# Schematic_TurtleAuth_-_Stm32GPG_2022-05-.net
KiCad netlist of a schematic drawn in EasyEDA
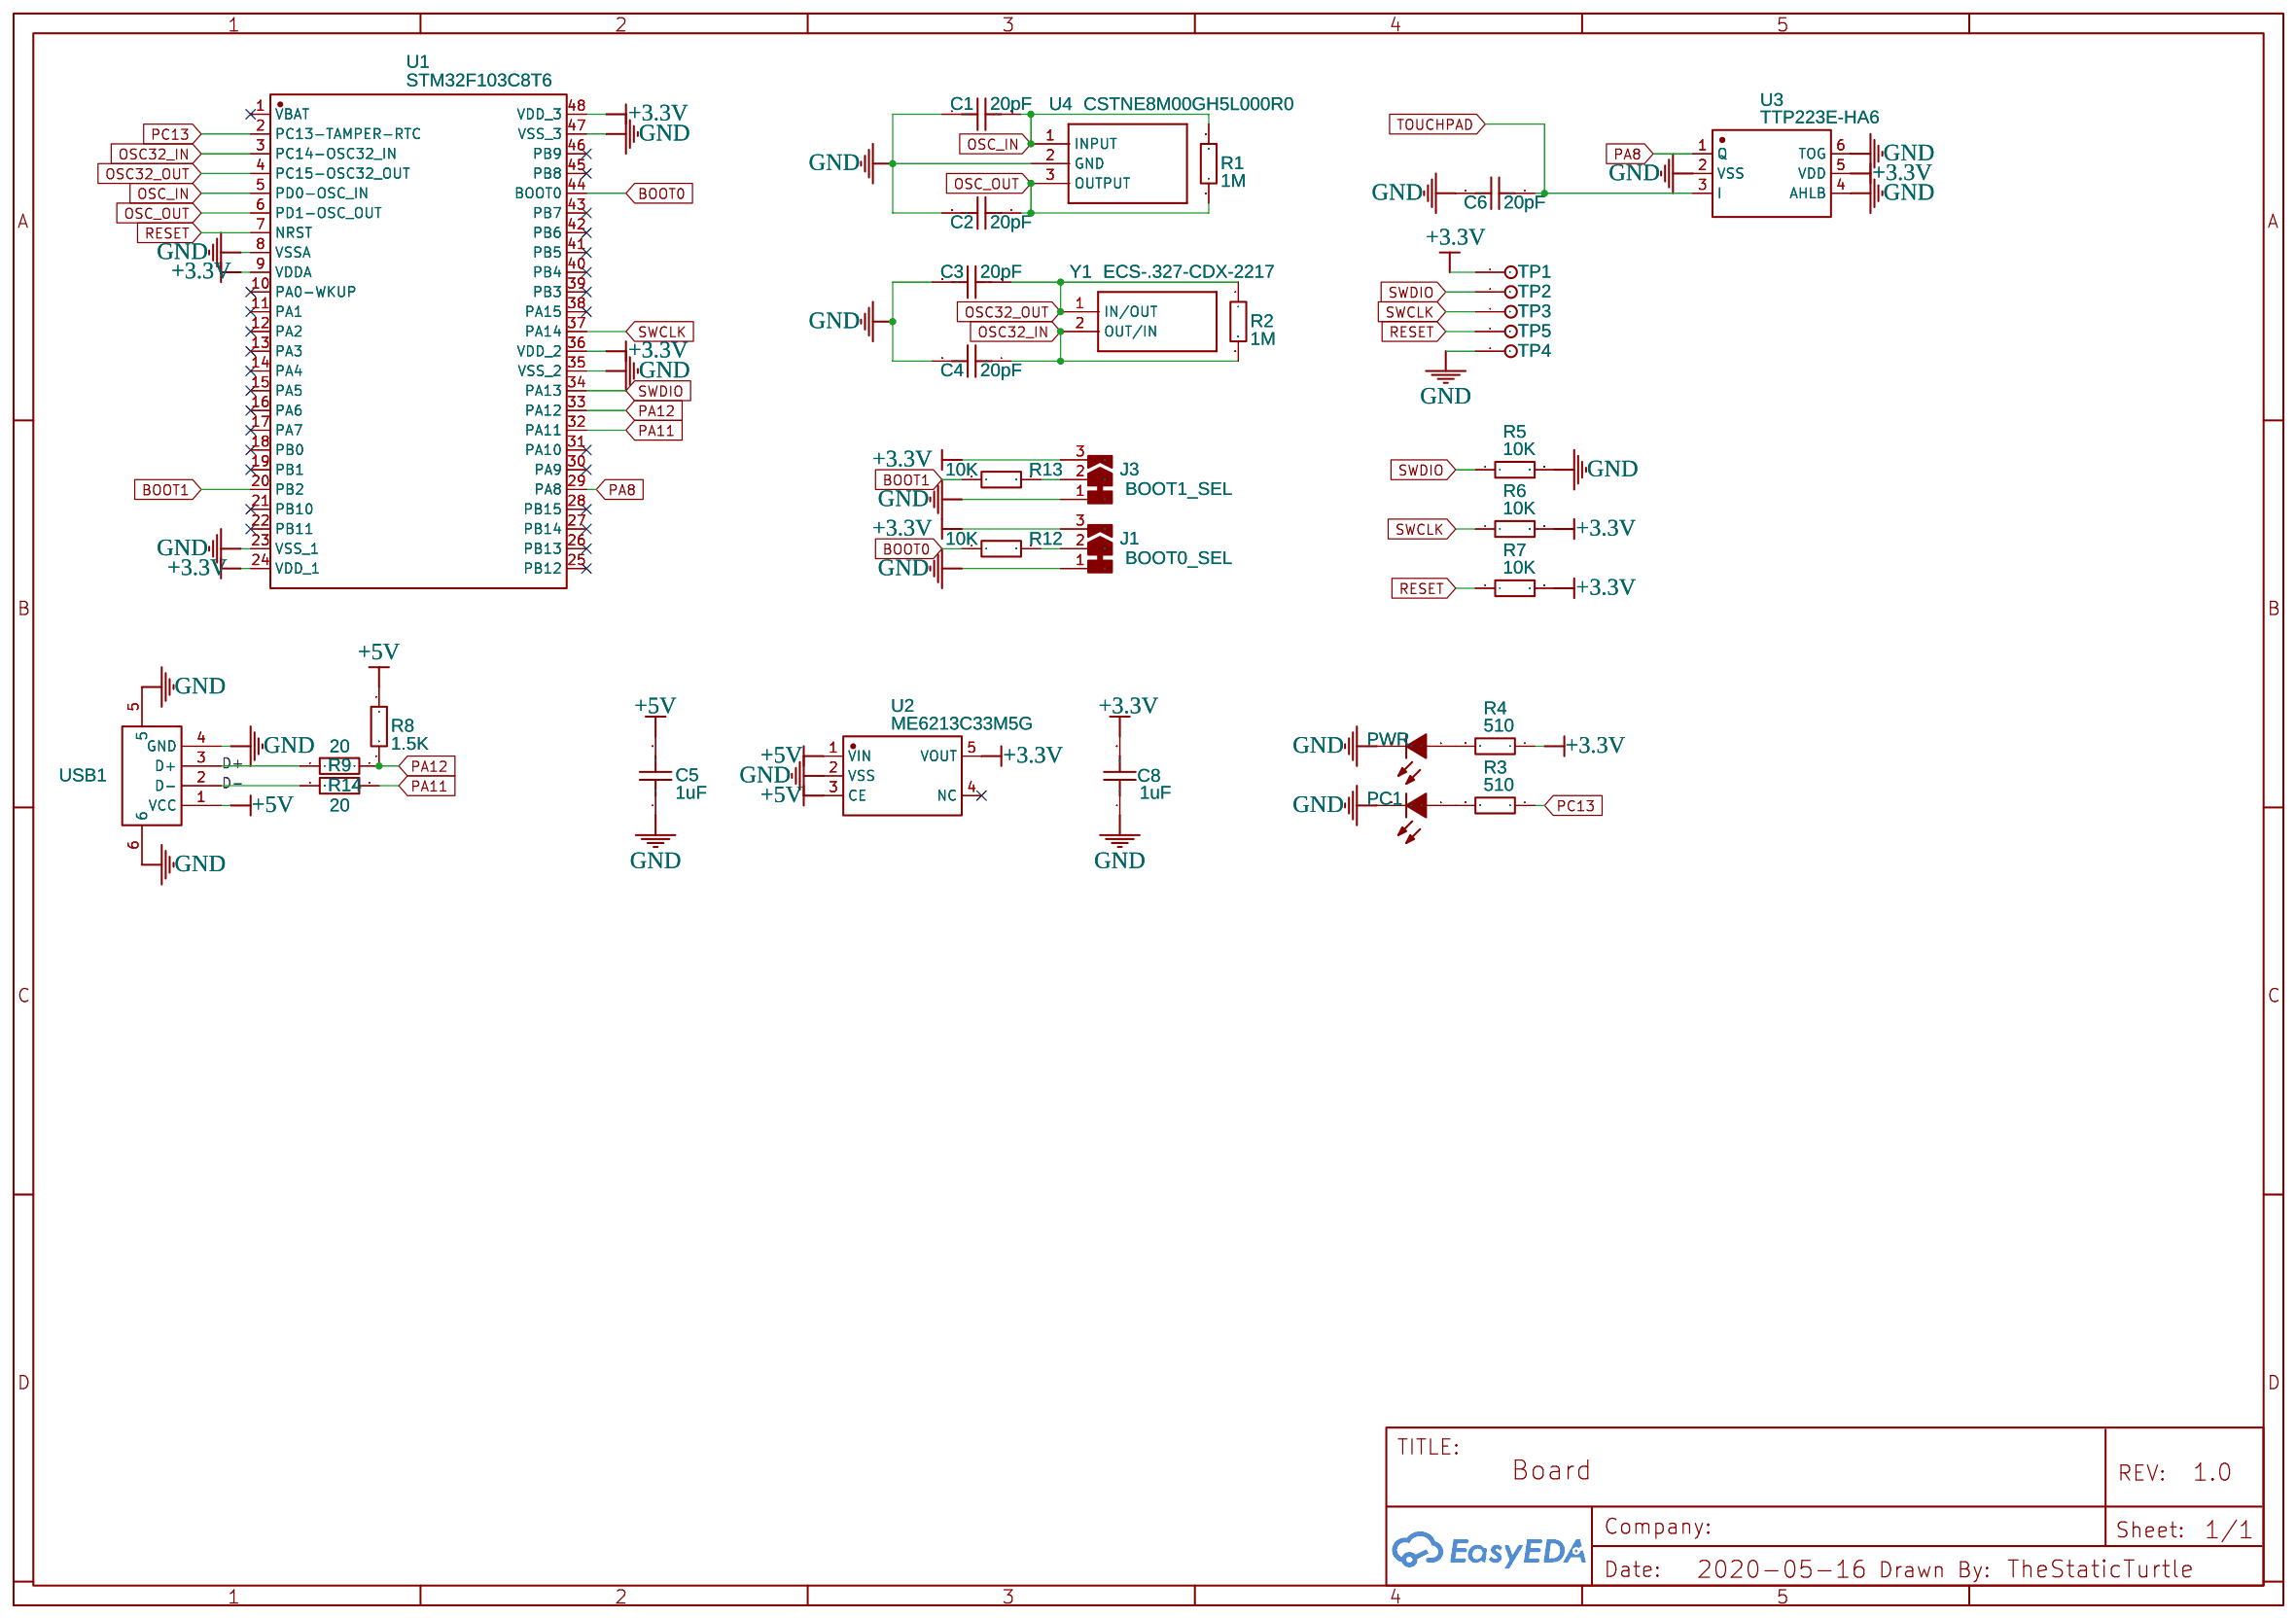
[diagram p0: schematic sheet]

(export (version "E")
  (design (tool "Eeschema 10.0.6"))
  (components
    (comp (ref "C1")
      (value "20pF")
      (fields
        (field (name "BOM_Manufacturer Part") "GJM0225C1C200JB01L")
        (field (name "BOM_Supplier Part") "81-GJM0225C1C200JB1L")
      )
      (libsource (lib "") (part "0603N200J500_1"))
    )
    (comp (ref "C2")
      (value "20pF")
      (fields
        (field (name "BOM_Manufacturer Part") "GJM0225C1C200JB01L")
        (field (name "BOM_Supplier Part") "81-GJM0225C1C200JB1L")
      )
      (libsource (lib "") (part "0603N200J500"))
    )
    (comp (ref "C3")
      (value "20pF")
      (fields
        (field (name "BOM_Manufacturer Part") "GJM0225C1C200JB01L")
        (field (name "BOM_Supplier Part") "81-GJM0225C1C200JB1L")
      )
      (libsource (lib "") (part "0603N200J500"))
    )
    (comp (ref "C4")
      (value "20pF")
      (fields
        (field (name "BOM_Manufacturer Part") "GJM0225C1C200JB01L")
        (field (name "BOM_Supplier Part") "81-GJM0225C1C200JB1L")
      )
      (libsource (lib "") (part "0603N200J500"))
    )
    (comp (ref "C5")
      (value "1uF")
      (fields
        (field (name "BOM_Manufacturer Part") "JMK105BJ105KV8F")
        (field (name "BOM_Supplier Part") "963-JMK105BJ105KV8F")
      )
      (libsource (lib "") (part "0603F105Z160"))
    )
    (comp (ref "C6")
      (value "20pF")
      (fields
        (field (name "BOM_Manufacturer Part") "GJM0225C1C200JB01L")
        (field (name "BOM_Supplier Part") "81-GJM0225C1C200JB1L")
      )
      (libsource (lib "") (part "0603N200J500"))
    )
    (comp (ref "C8")
      (value "1uF")
      (fields
        (field (name "BOM_Manufacturer Part") "JMK105BJ105KV8F")
        (field (name "BOM_Supplier Part") "963-JMK105BJ105KV8F")
      )
      (libsource (lib "") (part "0603F105Z160"))
    )
    (comp (ref "J1") (value "BOOT0_SEL") (libsource (lib "") (part "2-way SMD Arrow Selector (NC/NO)")))
    (comp (ref "J3") (value "BOOT1_SEL") (libsource (lib "") (part "2-way SMD Arrow Selector (NC/NO)")))
    (comp (ref "PC1")
      (value "FC-D1608HOK-600H")
      (fields
        (field (name "BOM_Manufacturer Part") "LTST-C194TBKT")
        (field (name "BOM_Supplier Part") "859-LTST-C194TBKT")
      )
      (libsource (lib "") (part "FC-D1608HOK-600H_1"))
    )
    (comp (ref "PWR")
      (value "FC-D1608HOK-600H")
      (fields
        (field (name "BOM_Manufacturer Part") "150060RS75000")
        (field (name "BOM_Supplier Part") "710-150060RS75000")
      )
      (libsource (lib "") (part "FC-D1608HOK-600H"))
    )
    (comp (ref "R1")
      (value "1M")
      (fields
        (field (name "BOM_Manufacturer Part") "RK73B1ETTP105J")
        (field (name "BOM_Supplier Part") "660-RK73B1ETTP105J")
      )
      (libsource (lib "") (part "0603WAJ0105T5E"))
    )
    (comp (ref "R2")
      (value "1M")
      (fields
        (field (name "BOM_Manufacturer Part") "RK73B1ETTP105J")
        (field (name "BOM_Supplier Part") "660-RK73B1ETTP105J")
      )
      (libsource (lib "") (part "0603WAJ0105T5E"))
    )
    (comp (ref "R3")
      (value "510")
      (fields
        (field (name "BOM_Manufacturer Part") "RC0402JR-13510RL")
        (field (name "BOM_Supplier Part") "603-RC0402JR-13510RL")
      )
      (libsource (lib "") (part "0603WAJ0511T5E"))
    )
    (comp (ref "R4")
      (value "510")
      (fields
        (field (name "BOM_Manufacturer Part") "RC0402JR-13510RL")
        (field (name "BOM_Supplier Part") "603-RC0402JR-13510RL")
      )
      (libsource (lib "") (part "0603WAJ0511T5E"))
    )
    (comp (ref "R5")
      (value "10K")
      (fields
        (field (name "BOM_Manufacturer Part") "RC0402FR-1310KL")
        (field (name "BOM_Supplier Part") "603-RC0402FR-1310KL")
      )
      (libsource (lib "") (part "0603WAJ0103T5E"))
    )
    (comp (ref "R6")
      (value "10K")
      (fields
        (field (name "BOM_Manufacturer Part") "RC0402FR-1310KL")
        (field (name "BOM_Supplier Part") "603-RC0402FR-1310KL")
      )
      (libsource (lib "") (part "0603WAJ0103T5E"))
    )
    (comp (ref "R7")
      (value "10K")
      (fields
        (field (name "BOM_Manufacturer Part") "RC0402FR-1310KL")
        (field (name "BOM_Supplier Part") "603-RC0402FR-1310KL")
      )
      (libsource (lib "") (part "0603WAJ0103T5E"))
    )
    (comp (ref "R8")
      (value "1.5K")
      (fields
        (field (name "BOM_Manufacturer Part") "RE0402DRE071K5L")
        (field (name "BOM_Supplier Part") "603-RE0402DRE071K5L")
      )
      (libsource (lib "") (part "0603WAJ0152T5E"))
    )
    (comp (ref "R9")
      (value "20")
      (fields
        (field (name "BOM_Manufacturer Part") "RC0402FR-7W20RL")
        (field (name "BOM_Supplier Part") "603-RC0402FR-7W20RL")
      )
      (libsource (lib "") (part "RTT03200JTP"))
    )
    (comp (ref "R12")
      (value "10K")
      (fields
        (field (name "BOM_Manufacturer Part") "RC0402FR-1310KL")
        (field (name "BOM_Supplier Part") "603-RC0402FR-1310KL")
      )
      (libsource (lib "") (part "0603WAJ0103T5E"))
    )
    (comp (ref "R13")
      (value "10K")
      (fields
        (field (name "BOM_Manufacturer Part") "RC0402FR-1310KL")
        (field (name "BOM_Supplier Part") "603-RC0402FR-1310KL")
      )
      (libsource (lib "") (part "0603WAJ0103T5E"))
    )
    (comp (ref "R14")
      (value "20")
      (fields
        (field (name "BOM_Manufacturer Part") "RC0402FR-7W20RL")
        (field (name "BOM_Supplier Part") "603-RC0402FR-7W20RL")
      )
      (libsource (lib "") (part "RTT03200JTP"))
    )
    (comp (ref "TP1") (value "Test Point") (libsource (lib "") (part "Test Point")))
    (comp (ref "TP2") (value "Test Point") (libsource (lib "") (part "Test Point")))
    (comp (ref "TP3") (value "Test Point") (libsource (lib "") (part "Test Point")))
    (comp (ref "TP4") (value "Test Point") (libsource (lib "") (part "Test Point")))
    (comp (ref "TP5") (value "Test Point") (libsource (lib "") (part "Test Point")))
    (comp (ref "U1")
      (value "STM32F103C8T6")
      (fields (field (name "BOM_Supplier Part") "C8734"))
      (libsource (lib "") (part "STM32F103C8T6"))
    )
    (comp (ref "U2")
      (value "ME6213C33M5G")
      (fields (field (name "BOM_Supplier Part") "C236666"))
      (libsource (lib "") (part "ME6213C33M5G"))
    )
    (comp (ref "U3")
      (value "TTP223E-HA6")
      (fields (field (name "BOM_Supplier Part") "C129459"))
      (libsource (lib "") (part "TTP223E-HA6"))
    )
    (comp (ref "U4")
      (value "CSTNE8M00GH5L000R0")
      (fields (field (name "BOM_Supplier Part") "81-CSTNE8M00GH5L000R"))
      (libsource (lib "") (part "CSTNE8M00GH5L000R0"))
    )
    (comp (ref "USB1")
      (value "U217-04XN-XXR84")
      (fields
        (field (name "BOM_Manufacturer Part") "USB1061-GF-L-A")
        (field (name "BOM_Supplier Part") "640-USB1061-GF-L-A")
      )
      (libsource (lib "") (part "U217-04XN-XXR84"))
    )
    (comp (ref "Y1")
      (value "ECS-.327-CDX-2217")
      (fields (field (name "BOM_Manufacturer Part") "520-ECS-327-CDX2217"))
      (libsource (lib "") (part "ECS-.327-CDX-2217"))
    )
  )
  (nets
    (net (code "1") (name "+3.3V") (class "Default")
      (node (ref "C8") (pin "2") (pinfunction "2_2") (pintype "unspecified"))
      (node (ref "J1") (pin "3") (pinfunction "3_3") (pintype "unspecified"))
      (node (ref "J3") (pin "3") (pinfunction "3_3") (pintype "unspecified"))
      (node (ref "R4") (pin "1") (pinfunction "1_1") (pintype "input"))
      (node (ref "R6") (pin "2") (pinfunction "2_2") (pintype "input"))
      (node (ref "R7") (pin "2") (pinfunction "2_2") (pintype "input"))
      (node (ref "TP1") (pin "1") (pinfunction "1_1") (pintype "unspecified"))
      (node (ref "U1") (pin "24") (pinfunction "VDD_1_24") (pintype "unspecified"))
      (node (ref "U1") (pin "36") (pinfunction "VDD_2_36") (pintype "unspecified"))
      (node (ref "U1") (pin "48") (pinfunction "VDD_3_48") (pintype "unspecified"))
      (node (ref "U1") (pin "9") (pinfunction "VDDA_9") (pintype "unspecified"))
      (node (ref "U2") (pin "5") (pinfunction "VOUT_5") (pintype "unspecified"))
      (node (ref "U3") (pin "5") (pinfunction "VDD_5") (pintype "unspecified"))
    )
    (net (code "2") (name "+5V") (class "Default")
      (node (ref "C5") (pin "2") (pinfunction "2_2") (pintype "unspecified"))
      (node (ref "R8") (pin "1") (pinfunction "1_1") (pintype "input"))
      (node (ref "U2") (pin "1") (pinfunction "VIN_1") (pintype "unspecified"))
      (node (ref "U2") (pin "3") (pinfunction "CE_3") (pintype "unspecified"))
      (node (ref "USB1") (pin "1") (pinfunction "VCC_1") (pintype "unspecified"))
    )
    (net (code "3") (name "/D+") (class "Default")
      (node (ref "R9") (pin "1") (pinfunction "1_1") (pintype "input"))
      (node (ref "USB1") (pin "3") (pinfunction "D+_3") (pintype "unspecified"))
    )
    (net (code "4") (name "/D-") (class "Default")
      (node (ref "R14") (pin "1") (pinfunction "1_1") (pintype "input"))
      (node (ref "USB1") (pin "2") (pinfunction "D-_2") (pintype "unspecified"))
    )
    (net (code "5") (name "BOOT0") (class "Default")
      (node (ref "R12") (pin "1") (pinfunction "1_1") (pintype "input"))
      (node (ref "U1") (pin "44") (pinfunction "BOOT0_44") (pintype "unspecified"))
    )
    (net (code "6") (name "BOOT1") (class "Default")
      (node (ref "R13") (pin "1") (pinfunction "1_1") (pintype "input"))
      (node (ref "U1") (pin "20") (pinfunction "PB2_20") (pintype "unspecified"))
    )
    (net (code "7") (name "GND") (class "Default")
      (node (ref "C1") (pin "1") (pinfunction "1_1") (pintype "unspecified"))
      (node (ref "C2") (pin "2") (pinfunction "2_2") (pintype "unspecified"))
      (node (ref "C3") (pin "2") (pinfunction "2_2") (pintype "unspecified"))
      (node (ref "C4") (pin "2") (pinfunction "2_2") (pintype "unspecified"))
      (node (ref "C5") (pin "1") (pinfunction "1_1") (pintype "unspecified"))
      (node (ref "C6") (pin "2") (pinfunction "2_2") (pintype "unspecified"))
      (node (ref "C8") (pin "1") (pinfunction "1_1") (pintype "unspecified"))
      (node (ref "J1") (pin "1") (pinfunction "1_1") (pintype "unspecified"))
      (node (ref "J3") (pin "1") (pinfunction "1_1") (pintype "unspecified"))
      (node (ref "PC1") (pin "2") (pinfunction "K_2") (pintype "input"))
      (node (ref "PWR") (pin "2") (pinfunction "K_2") (pintype "input"))
      (node (ref "R5") (pin "2") (pinfunction "2_2") (pintype "input"))
      (node (ref "TP4") (pin "1") (pinfunction "1_1") (pintype "unspecified"))
      (node (ref "U1") (pin "23") (pinfunction "VSS_1_23") (pintype "unspecified"))
      (node (ref "U1") (pin "35") (pinfunction "VSS_2_35") (pintype "unspecified"))
      (node (ref "U1") (pin "47") (pinfunction "VSS_3_47") (pintype "unspecified"))
      (node (ref "U1") (pin "8") (pinfunction "VSSA_8") (pintype "unspecified"))
      (node (ref "U2") (pin "2") (pinfunction "VSS_2") (pintype "unspecified"))
      (node (ref "U3") (pin "2") (pinfunction "VSS_2") (pintype "unspecified"))
      (node (ref "U3") (pin "4") (pinfunction "AHLB_4") (pintype "unspecified"))
      (node (ref "U3") (pin "6") (pinfunction "TOG_6") (pintype "unspecified"))
      (node (ref "U4") (pin "2") (pinfunction "GND_2") (pintype "bidirectional"))
      (node (ref "USB1") (pin "4") (pinfunction "GND_4") (pintype "unspecified"))
      (node (ref "USB1") (pin "5") (pinfunction "5_5") (pintype "unspecified"))
      (node (ref "USB1") (pin "6") (pinfunction "6_6") (pintype "unspecified"))
    )
    (net (code "8") (name "Net-(J1-Pad2)") (class "Default")
      (node (ref "J1") (pin "2") (pinfunction "2_2") (pintype "unspecified"))
      (node (ref "R12") (pin "2") (pinfunction "2_2") (pintype "input"))
    )
    (net (code "9") (name "Net-(J3-Pad2)") (class "Default")
      (node (ref "J3") (pin "2") (pinfunction "2_2") (pintype "unspecified"))
      (node (ref "R13") (pin "2") (pinfunction "2_2") (pintype "input"))
    )
    (net (code "10") (name "Net-(PC1-A)") (class "Default")
      (node (ref "PC1") (pin "1") (pinfunction "A_1") (pintype "input"))
      (node (ref "R3") (pin "2") (pinfunction "2_2") (pintype "input"))
    )
    (net (code "11") (name "Net-(PWR-A)") (class "Default")
      (node (ref "PWR") (pin "1") (pinfunction "A_1") (pintype "input"))
      (node (ref "R4") (pin "2") (pinfunction "2_2") (pintype "input"))
    )
    (net (code "12") (name "OSC32_IN") (class "Default")
      (node (ref "C4") (pin "1") (pinfunction "1_1") (pintype "unspecified"))
      (node (ref "R2") (pin "2") (pinfunction "2_2") (pintype "input"))
      (node (ref "U1") (pin "3") (pinfunction "PC14-OSC32_IN_3") (pintype "unspecified"))
      (node (ref "Y1") (pin "2") (pinfunction "OUT/IN_2") (pintype "bidirectional"))
    )
    (net (code "13") (name "OSC32_OUT") (class "Default")
      (node (ref "C3") (pin "1") (pinfunction "1_1") (pintype "unspecified"))
      (node (ref "R2") (pin "1") (pinfunction "1_1") (pintype "input"))
      (node (ref "U1") (pin "4") (pinfunction "PC15-OSC32_OUT_4") (pintype "unspecified"))
      (node (ref "Y1") (pin "1") (pinfunction "IN/OUT_1") (pintype "bidirectional"))
    )
    (net (code "14") (name "OSC_IN") (class "Default")
      (node (ref "C1") (pin "2") (pinfunction "2_2") (pintype "unspecified"))
      (node (ref "R1") (pin "1") (pinfunction "1_1") (pintype "input"))
      (node (ref "U1") (pin "5") (pinfunction "PD0-OSC_IN_5") (pintype "unspecified"))
      (node (ref "U4") (pin "1") (pinfunction "INPUT_1") (pintype "bidirectional"))
    )
    (net (code "15") (name "OSC_OUT") (class "Default")
      (node (ref "C2") (pin "1") (pinfunction "1_1") (pintype "unspecified"))
      (node (ref "R1") (pin "2") (pinfunction "2_2") (pintype "input"))
      (node (ref "U1") (pin "6") (pinfunction "PD1-OSC_OUT_6") (pintype "unspecified"))
      (node (ref "U4") (pin "3") (pinfunction "OUTPUT_3") (pintype "bidirectional"))
    )
    (net (code "16") (name "PA8") (class "Default")
      (node (ref "U1") (pin "29") (pinfunction "PA8_29") (pintype "unspecified"))
      (node (ref "U3") (pin "1") (pinfunction "Q_1") (pintype "unspecified"))
    )
    (net (code "17") (name "PA11") (class "Default")
      (node (ref "R14") (pin "2") (pinfunction "2_2") (pintype "input"))
      (node (ref "U1") (pin "32") (pinfunction "PA11_32") (pintype "unspecified"))
    )
    (net (code "18") (name "PA12") (class "Default")
      (node (ref "R8") (pin "2") (pinfunction "2_2") (pintype "input"))
      (node (ref "R9") (pin "2") (pinfunction "2_2") (pintype "input"))
      (node (ref "U1") (pin "33") (pinfunction "PA12_33") (pintype "unspecified"))
    )
    (net (code "19") (name "PC13") (class "Default")
      (node (ref "R3") (pin "1") (pinfunction "1_1") (pintype "input"))
      (node (ref "U1") (pin "2") (pinfunction "PC13-TAMPER-RTC_2") (pintype "unspecified"))
    )
    (net (code "20") (name "RESET") (class "Default")
      (node (ref "R7") (pin "1") (pinfunction "1_1") (pintype "input"))
      (node (ref "TP5") (pin "1") (pinfunction "1_1") (pintype "unspecified"))
      (node (ref "U1") (pin "7") (pinfunction "NRST_7") (pintype "unspecified"))
    )
    (net (code "21") (name "SWCLK") (class "Default")
      (node (ref "R6") (pin "1") (pinfunction "1_1") (pintype "input"))
      (node (ref "TP3") (pin "1") (pinfunction "1_1") (pintype "unspecified"))
      (node (ref "U1") (pin "37") (pinfunction "PA14_37") (pintype "unspecified"))
    )
    (net (code "22") (name "SWDIO") (class "Default")
      (node (ref "R5") (pin "1") (pinfunction "1_1") (pintype "input"))
      (node (ref "TP2") (pin "1") (pinfunction "1_1") (pintype "unspecified"))
      (node (ref "U1") (pin "34") (pinfunction "PA13_34") (pintype "unspecified"))
    )
    (net (code "23") (name "TOUCHPAD") (class "Default")
      (node (ref "C6") (pin "1") (pinfunction "1_1") (pintype "unspecified"))
      (node (ref "U3") (pin "3") (pinfunction "I_3") (pintype "unspecified"))
    )
    (net (code "24") (name "unconnected-(U1-PA0-WKUP-Pad10)") (class "Default")
      (node (ref "U1") (pin "10") (pinfunction "PA0-WKUP_10") (pintype "unspecified+no_connect"))
    )
    (net (code "25") (name "unconnected-(U1-PA1-Pad11)") (class "Default")
      (node (ref "U1") (pin "11") (pinfunction "PA1_11") (pintype "unspecified+no_connect"))
    )
    (net (code "26") (name "unconnected-(U1-PA2-Pad12)") (class "Default")
      (node (ref "U1") (pin "12") (pinfunction "PA2_12") (pintype "unspecified+no_connect"))
    )
    (net (code "27") (name "unconnected-(U1-PA3-Pad13)") (class "Default")
      (node (ref "U1") (pin "13") (pinfunction "PA3_13") (pintype "unspecified+no_connect"))
    )
    (net (code "28") (name "unconnected-(U1-PA4-Pad14)") (class "Default")
      (node (ref "U1") (pin "14") (pinfunction "PA4_14") (pintype "unspecified+no_connect"))
    )
    (net (code "29") (name "unconnected-(U1-PA5-Pad15)") (class "Default")
      (node (ref "U1") (pin "15") (pinfunction "PA5_15") (pintype "unspecified+no_connect"))
    )
    (net (code "30") (name "unconnected-(U1-PA6-Pad16)") (class "Default")
      (node (ref "U1") (pin "16") (pinfunction "PA6_16") (pintype "unspecified+no_connect"))
    )
    (net (code "31") (name "unconnected-(U1-PA7-Pad17)") (class "Default")
      (node (ref "U1") (pin "17") (pinfunction "PA7_17") (pintype "unspecified+no_connect"))
    )
    (net (code "32") (name "unconnected-(U1-PA9-Pad30)") (class "Default")
      (node (ref "U1") (pin "30") (pinfunction "PA9_30") (pintype "unspecified+no_connect"))
    )
    (net (code "33") (name "unconnected-(U1-PA10-Pad31)") (class "Default")
      (node (ref "U1") (pin "31") (pinfunction "PA10_31") (pintype "unspecified+no_connect"))
    )
    (net (code "34") (name "unconnected-(U1-PA15-Pad38)") (class "Default")
      (node (ref "U1") (pin "38") (pinfunction "PA15_38") (pintype "unspecified+no_connect"))
    )
    (net (code "35") (name "unconnected-(U1-PB0-Pad18)") (class "Default")
      (node (ref "U1") (pin "18") (pinfunction "PB0_18") (pintype "unspecified+no_connect"))
    )
    (net (code "36") (name "unconnected-(U1-PB1-Pad19)") (class "Default")
      (node (ref "U1") (pin "19") (pinfunction "PB1_19") (pintype "unspecified+no_connect"))
    )
    (net (code "37") (name "unconnected-(U1-PB3-Pad39)") (class "Default")
      (node (ref "U1") (pin "39") (pinfunction "PB3_39") (pintype "unspecified+no_connect"))
    )
    (net (code "38") (name "unconnected-(U1-PB4-Pad40)") (class "Default")
      (node (ref "U1") (pin "40") (pinfunction "PB4_40") (pintype "unspecified+no_connect"))
    )
    (net (code "39") (name "unconnected-(U1-PB5-Pad41)") (class "Default")
      (node (ref "U1") (pin "41") (pinfunction "PB5_41") (pintype "unspecified+no_connect"))
    )
    (net (code "40") (name "unconnected-(U1-PB6-Pad42)") (class "Default")
      (node (ref "U1") (pin "42") (pinfunction "PB6_42") (pintype "unspecified+no_connect"))
    )
    (net (code "41") (name "unconnected-(U1-PB7-Pad43)") (class "Default")
      (node (ref "U1") (pin "43") (pinfunction "PB7_43") (pintype "unspecified+no_connect"))
    )
    (net (code "42") (name "unconnected-(U1-PB8-Pad45)") (class "Default")
      (node (ref "U1") (pin "45") (pinfunction "PB8_45") (pintype "unspecified+no_connect"))
    )
    (net (code "43") (name "unconnected-(U1-PB9-Pad46)") (class "Default")
      (node (ref "U1") (pin "46") (pinfunction "PB9_46") (pintype "unspecified+no_connect"))
    )
    (net (code "44") (name "unconnected-(U1-PB10-Pad21)") (class "Default")
      (node (ref "U1") (pin "21") (pinfunction "PB10_21") (pintype "unspecified+no_connect"))
    )
    (net (code "45") (name "unconnected-(U1-PB11-Pad22)") (class "Default")
      (node (ref "U1") (pin "22") (pinfunction "PB11_22") (pintype "unspecified+no_connect"))
    )
    (net (code "46") (name "unconnected-(U1-PB12-Pad25)") (class "Default")
      (node (ref "U1") (pin "25") (pinfunction "PB12_25") (pintype "unspecified+no_connect"))
    )
    (net (code "47") (name "unconnected-(U1-PB13-Pad26)") (class "Default")
      (node (ref "U1") (pin "26") (pinfunction "PB13_26") (pintype "unspecified+no_connect"))
    )
    (net (code "48") (name "unconnected-(U1-PB14-Pad27)") (class "Default")
      (node (ref "U1") (pin "27") (pinfunction "PB14_27") (pintype "unspecified+no_connect"))
    )
    (net (code "49") (name "unconnected-(U1-PB15-Pad28)") (class "Default")
      (node (ref "U1") (pin "28") (pinfunction "PB15_28") (pintype "unspecified+no_connect"))
    )
    (net (code "50") (name "unconnected-(U1-VBAT-Pad1)") (class "Default")
      (node (ref "U1") (pin "1") (pinfunction "VBAT_1") (pintype "unspecified+no_connect"))
    )
    (net (code "51") (name "unconnected-(U2-NC-Pad4)") (class "Default")
      (node (ref "U2") (pin "4") (pinfunction "NC_4") (pintype "unspecified+no_connect"))
    )
  )
)
